# TM8_EVO_Mom.net
KiCad netlist of a schematic drawn in EAGLE
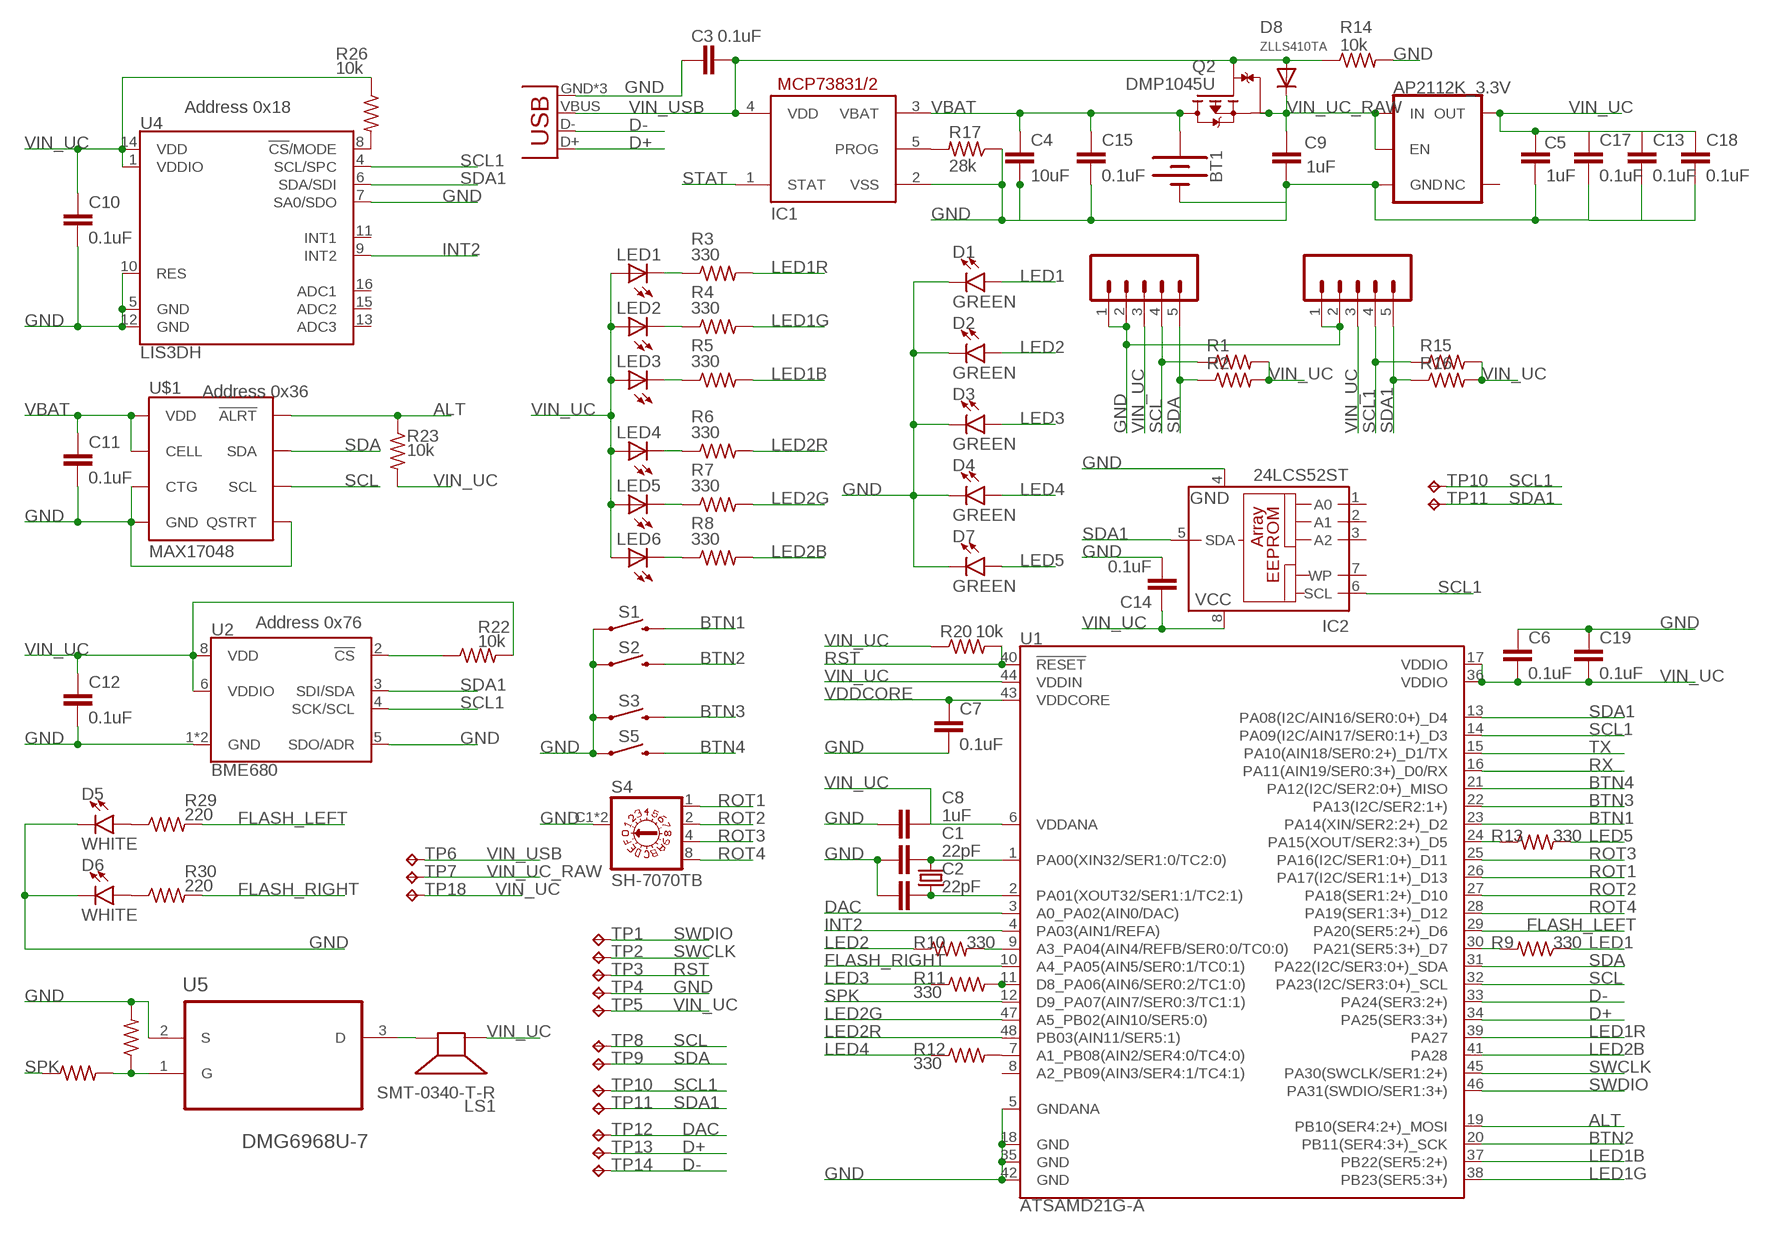
[diagram p0: schematic, sheet 1]

(export (version "E")
  (design (tool "Eeschema 10.0.6"))
  (components
    (comp (ref "AP2112K_3.3V")
      (value "3.3V")
      (footprint "eagle-import:SOT23-5")
      (libsource (lib "eagle-import") (part "V_REG_AP2112K-3.3V"))
    )
    (comp (ref "BT1")
      (value "BATTERY-20MM_SMD_4LEGS_OVERPASTE_INNER")
      (footprint "eagle-import:BATTCON_20MM_4LEGS_OVERPASTE_INNER")
      (libsource (lib "eagle-import") (part "BATTERY-20MM_SMD_4LEGS_OVERPASTE_INNER"))
    )
    (comp (ref "C1")
      (value "22pF")
      (footprint "eagle-import:C0402")
      (libsource (lib "eagle-import") (part "C-EUC0402"))
    )
    (comp (ref "C2")
      (value "22pF")
      (footprint "eagle-import:C0402")
      (libsource (lib "eagle-import") (part "C-EUC0402"))
    )
    (comp (ref "C3")
      (value "0.1uF")
      (footprint "eagle-import:C0402")
      (libsource (lib "eagle-import") (part "C-EUC0402"))
    )
    (comp (ref "C4")
      (value "10uF")
      (footprint "eagle-import:C0402")
      (libsource (lib "eagle-import") (part "C-EUC0402"))
    )
    (comp (ref "C5")
      (value "1uF")
      (footprint "eagle-import:C0402")
      (libsource (lib "eagle-import") (part "C-EUC0402"))
    )
    (comp (ref "C6")
      (value "0.1uF")
      (footprint "eagle-import:C0402")
      (libsource (lib "eagle-import") (part "C-EUC0402"))
    )
    (comp (ref "C7")
      (value "0.1uF")
      (footprint "eagle-import:C0402")
      (libsource (lib "eagle-import") (part "C-EUC0402"))
    )
    (comp (ref "C8")
      (value "1uF")
      (footprint "eagle-import:C0402")
      (libsource (lib "eagle-import") (part "C-EUC0402"))
    )
    (comp (ref "C9")
      (value "1uF")
      (footprint "eagle-import:C0402")
      (libsource (lib "eagle-import") (part "C-EUC0402"))
    )
    (comp (ref "C10")
      (value "0.1uF")
      (footprint "eagle-import:C0402")
      (libsource (lib "eagle-import") (part "C-EUC0402"))
    )
    (comp (ref "C11")
      (value "0.1uF")
      (footprint "eagle-import:C0402")
      (libsource (lib "eagle-import") (part "C-EUC0402"))
    )
    (comp (ref "C12")
      (value "0.1uF")
      (footprint "eagle-import:C0402")
      (libsource (lib "eagle-import") (part "C-EUC0402"))
    )
    (comp (ref "C13")
      (value "0.1uF")
      (footprint "eagle-import:C0402")
      (libsource (lib "eagle-import") (part "C-EUC0402"))
    )
    (comp (ref "C14")
      (value "0.1uF")
      (footprint "eagle-import:C0402")
      (libsource (lib "eagle-import") (part "C-EUC0402"))
    )
    (comp (ref "C15")
      (value "0.1uF")
      (footprint "eagle-import:C0402")
      (libsource (lib "eagle-import") (part "C-EUC0402"))
    )
    (comp (ref "C17")
      (value "0.1uF")
      (footprint "eagle-import:C0402")
      (libsource (lib "eagle-import") (part "C-EUC0402"))
    )
    (comp (ref "C18")
      (value "0.1uF")
      (footprint "eagle-import:C0402")
      (libsource (lib "eagle-import") (part "C-EUC0402"))
    )
    (comp (ref "C19")
      (value "0.1uF")
      (footprint "eagle-import:C0402")
      (libsource (lib "eagle-import") (part "C-EUC0402"))
    )
    (comp (ref "D1")
      (value "GREEN")
      (footprint "eagle-import:LED-1206")
      (libsource (lib "eagle-import") (part "LED-GREEN1206"))
    )
    (comp (ref "D2")
      (value "GREEN")
      (footprint "eagle-import:LED-1206")
      (libsource (lib "eagle-import") (part "LED-GREEN1206"))
    )
    (comp (ref "D3")
      (value "GREEN")
      (footprint "eagle-import:LED-1206")
      (libsource (lib "eagle-import") (part "LED-GREEN1206"))
    )
    (comp (ref "D4")
      (value "GREEN")
      (footprint "eagle-import:LED-1206")
      (libsource (lib "eagle-import") (part "LED-GREEN1206"))
    )
    (comp (ref "D5")
      (value "WHITE")
      (footprint "eagle-import:LED-1206")
      (libsource (lib "eagle-import") (part "LED-WHITE1206"))
    )
    (comp (ref "D6")
      (value "WHITE")
      (footprint "eagle-import:LED-1206")
      (libsource (lib "eagle-import") (part "LED-WHITE1206"))
    )
    (comp (ref "D7")
      (value "GREEN")
      (footprint "eagle-import:LED-1206")
      (libsource (lib "eagle-import") (part "LED-GREEN1206"))
    )
    (comp (ref "D8")
      (value "ZLLS410TA")
      (footprint "eagle-import:SOD-323F")
      (libsource (lib "eagle-import") (part "DIODESOD-323F"))
    )
    (comp (ref "IC1")
      (value "MCP73831/OT")
      (footprint "eagle-import:SOT23-5L")
      (libsource (lib "eagle-import") (part "MCP73831/OT"))
    )
    (comp (ref "IC2")
      (value "24LCS52ST")
      (footprint "eagle-import:TSSOP8")
      (fields (field (name "MF") "MICROCHIP") (field (name "MPN") "24LCS52T/ST"))
      (libsource (lib "eagle-import") (part "24STLCS52"))
    )
    (comp (ref "JP2")
      (value "USB-MICROB")
      (footprint "eagle-import:USB-MICROB")
      (libsource (lib "eagle-import") (part "USB-MICROB"))
    )
    (comp (ref "LCD1")
      (value "CONN_05VERT_FEMALE_HEADER")
      (footprint "eagle-import:1X05_SMD_VERTICAL_COMBO")
      (libsource (lib "eagle-import") (part "CONN_05VERT_FEMALE_HEADER"))
    )
    (comp (ref "LCD2")
      (value "CONN_05VERT_FEMALE_HEADER")
      (footprint "eagle-import:1X05_SMD_VERTICAL_COMBO")
      (libsource (lib "eagle-import") (part "CONN_05VERT_FEMALE_HEADER"))
    )
    (comp (ref "LED1")
      (value "LEDCHIPLED_0805")
      (footprint "eagle-import:CHIPLED_0805")
      (libsource (lib "eagle-import") (part "LEDCHIPLED_0805"))
    )
    (comp (ref "LED2")
      (value "LEDCHIPLED_0805")
      (footprint "eagle-import:CHIPLED_0805")
      (libsource (lib "eagle-import") (part "LEDCHIPLED_0805"))
    )
    (comp (ref "LED3")
      (value "LEDCHIPLED_0805")
      (footprint "eagle-import:CHIPLED_0805")
      (libsource (lib "eagle-import") (part "LEDCHIPLED_0805"))
    )
    (comp (ref "LED4")
      (value "LEDCHIPLED_0805")
      (footprint "eagle-import:CHIPLED_0805")
      (libsource (lib "eagle-import") (part "LEDCHIPLED_0805"))
    )
    (comp (ref "LED5")
      (value "LEDCHIPLED_0805")
      (footprint "eagle-import:CHIPLED_0805")
      (libsource (lib "eagle-import") (part "LEDCHIPLED_0805"))
    )
    (comp (ref "LED6")
      (value "LEDCHIPLED_0805")
      (footprint "eagle-import:CHIPLED_0805")
      (libsource (lib "eagle-import") (part "LEDCHIPLED_0805"))
    )
    (comp (ref "LS1")
      (value "SMT-0340-T-R")
      (footprint "eagle-import:XDCR_SMT-0340-T-R")
      (fields (field (name "MANUFACTURER") "Pui Audio"))
      (libsource (lib "eagle-import") (part "SMT-0340-T-R"))
    )
    (comp (ref "Q2")
      (value "DMP1045U")
      (footprint "eagle-import:SOT91P240X110-3N")
      (fields (field (name "MF") "Diodes Inc."))
      (libsource (lib "eagle-import") (part "DMP1045U"))
    )
    (comp (ref "R1")
      (value "R-US_R0402")
      (footprint "eagle-import:R0402")
      (libsource (lib "eagle-import") (part "adafruit_25768682_R-US_R0402"))
    )
    (comp (ref "R2")
      (value "R-US_R0402")
      (footprint "eagle-import:R0402")
      (libsource (lib "eagle-import") (part "adafruit_25768682_R-US_R0402"))
    )
    (comp (ref "R3")
      (value "330")
      (footprint "eagle-import:R0402")
      (libsource (lib "eagle-import") (part "rcl_334_R-US_R0402"))
    )
    (comp (ref "R4")
      (value "330")
      (footprint "eagle-import:R0402")
      (libsource (lib "eagle-import") (part "rcl_334_R-US_R0402"))
    )
    (comp (ref "R5")
      (value "330")
      (footprint "eagle-import:R0402")
      (libsource (lib "eagle-import") (part "rcl_334_R-US_R0402"))
    )
    (comp (ref "R6")
      (value "330")
      (footprint "eagle-import:R0402")
      (libsource (lib "eagle-import") (part "rcl_334_R-US_R0402"))
    )
    (comp (ref "R7")
      (value "330")
      (footprint "eagle-import:R0402")
      (libsource (lib "eagle-import") (part "rcl_334_R-US_R0402"))
    )
    (comp (ref "R8")
      (value "330")
      (footprint "eagle-import:R0402")
      (libsource (lib "eagle-import") (part "rcl_334_R-US_R0402"))
    )
    (comp (ref "R9")
      (value "330")
      (footprint "eagle-import:R0402")
      (libsource (lib "eagle-import") (part "rcl_334_R-US_R0402"))
    )
    (comp (ref "R10")
      (value "330")
      (footprint "eagle-import:R0402")
      (libsource (lib "eagle-import") (part "rcl_334_R-US_R0402"))
    )
    (comp (ref "R11")
      (value "330")
      (footprint "eagle-import:R0402")
      (libsource (lib "eagle-import") (part "rcl_334_R-US_R0402"))
    )
    (comp (ref "R12")
      (value "330")
      (footprint "eagle-import:R0402")
      (libsource (lib "eagle-import") (part "rcl_334_R-US_R0402"))
    )
    (comp (ref "R13")
      (value "330")
      (footprint "eagle-import:R0402")
      (libsource (lib "eagle-import") (part "rcl_334_R-US_R0402"))
    )
    (comp (ref "R14")
      (value "10k")
      (footprint "eagle-import:R0402")
      (libsource (lib "eagle-import") (part "R-US_R0402"))
    )
    (comp (ref "R15")
      (value "R-US_R0402")
      (footprint "eagle-import:R0402")
      (libsource (lib "eagle-import") (part "adafruit_25768682_R-US_R0402"))
    )
    (comp (ref "R16")
      (value "R-US_R0402")
      (footprint "eagle-import:R0402")
      (libsource (lib "eagle-import") (part "adafruit_25768682_R-US_R0402"))
    )
    (comp (ref "R17")
      (value "28k")
      (footprint "eagle-import:R0402")
      (libsource (lib "eagle-import") (part "adafruit_25768682_R-US_R0402"))
    )
    (comp (ref "R18")
      (value "220")
      (footprint "eagle-import:R0402")
      (libsource (lib "eagle-import") (part "rcl_334_R-US_R0402"))
    )
    (comp (ref "R19")
      (value "220")
      (footprint "eagle-import:R0402")
      (libsource (lib "eagle-import") (part "rcl_334_R-US_R0402"))
    )
    (comp (ref "R20")
      (value "10k")
      (footprint "eagle-import:R0402")
      (libsource (lib "eagle-import") (part "adafruit_25768682_R-US_R0402"))
    )
    (comp (ref "R22")
      (value "10k")
      (footprint "eagle-import:R0402")
      (libsource (lib "eagle-import") (part "rcl_334_R-US_R0402"))
    )
    (comp (ref "R23")
      (value "10k")
      (footprint "eagle-import:R0402")
      (libsource (lib "eagle-import") (part "rcl_334_R-US_R0402"))
    )
    (comp (ref "R26")
      (value "10k")
      (footprint "eagle-import:R0402")
      (libsource (lib "eagle-import") (part "rcl_334_R-US_R0402"))
    )
    (comp (ref "R29")
      (value "220")
      (footprint "eagle-import:R0402")
      (libsource (lib "eagle-import") (part "rcl_334_R-US_R0402"))
    )
    (comp (ref "R30")
      (value "220")
      (footprint "eagle-import:R0402")
      (libsource (lib "eagle-import") (part "rcl_334_R-US_R0402"))
    )
    (comp (ref "S1")
      (value "MOMENTARY-SWITCH-SPST-SMD-6.0X3.5MM")
      (footprint "eagle-import:TACTILE_SWITCH_SMD_6.0X3.5MM")
      (libsource (lib "eagle-import") (part "MOMENTARY-SWITCH-SPST-SMD-6.0X3.5MM"))
    )
    (comp (ref "S2")
      (value "MOMENTARY-SWITCH-SPST-SMD-6.0X3.5MM")
      (footprint "eagle-import:TACTILE_SWITCH_SMD_6.0X3.5MM")
      (libsource (lib "eagle-import") (part "MOMENTARY-SWITCH-SPST-SMD-6.0X3.5MM"))
    )
    (comp (ref "S3")
      (value "MOMENTARY-SWITCH-SPST-SMD-6.0X3.5MM")
      (footprint "eagle-import:TACTILE_SWITCH_SMD_6.0X3.5MM")
      (libsource (lib "eagle-import") (part "MOMENTARY-SWITCH-SPST-SMD-6.0X3.5MM"))
    )
    (comp (ref "S4")
      (value "SH-7070TB")
      (footprint "eagle-import:SH-7070B")
      (fields (field (name "MF") "Nidec Copal"))
      (libsource (lib "eagle-import") (part "SH-7070TB"))
    )
    (comp (ref "S5")
      (value "MOMENTARY-SWITCH-SPST-SMD-6.0X3.5MM")
      (footprint "eagle-import:TACTILE_SWITCH_SMD_6.0X3.5MM")
      (libsource (lib "eagle-import") (part "MOMENTARY-SWITCH-SPST-SMD-6.0X3.5MM"))
    )
    (comp (ref "TP1")
      (value "TPTP14R")
      (footprint "eagle-import:TP14R")
      (libsource (lib "eagle-import") (part "TPTP14R"))
    )
    (comp (ref "TP2")
      (value "TPTP14R")
      (footprint "eagle-import:TP14R")
      (libsource (lib "eagle-import") (part "TPTP14R"))
    )
    (comp (ref "TP3")
      (value "TPTP14R")
      (footprint "eagle-import:TP14R")
      (libsource (lib "eagle-import") (part "TPTP14R"))
    )
    (comp (ref "TP4")
      (value "TPTP14R")
      (footprint "eagle-import:TP14R")
      (libsource (lib "eagle-import") (part "TPTP14R"))
    )
    (comp (ref "TP5")
      (value "TPTP14R")
      (footprint "eagle-import:TP14R")
      (libsource (lib "eagle-import") (part "TPTP14R"))
    )
    (comp (ref "TP6")
      (value "TPTP14R")
      (footprint "eagle-import:TP14R")
      (libsource (lib "eagle-import") (part "TPTP14R"))
    )
    (comp (ref "TP7")
      (value "TPTP14R")
      (footprint "eagle-import:TP14R")
      (libsource (lib "eagle-import") (part "TPTP14R"))
    )
    (comp (ref "TP8")
      (value "TPTP14R")
      (footprint "eagle-import:TP14R")
      (libsource (lib "eagle-import") (part "TPTP14R"))
    )
    (comp (ref "TP9")
      (value "TPTP14R")
      (footprint "eagle-import:TP14R")
      (libsource (lib "eagle-import") (part "TPTP14R"))
    )
    (comp (ref "TP10")
      (value "TPTP14R")
      (footprint "eagle-import:TP14R")
      (libsource (lib "eagle-import") (part "TPTP14R"))
    )
    (comp (ref "TP11")
      (value "TPTP14R")
      (footprint "eagle-import:TP14R")
      (libsource (lib "eagle-import") (part "TPTP14R"))
    )
    (comp (ref "TP12")
      (value "TPTP14R")
      (footprint "eagle-import:TP14R")
      (libsource (lib "eagle-import") (part "TPTP14R"))
    )
    (comp (ref "TP13")
      (value "TPTP14R")
      (footprint "eagle-import:TP14R")
      (libsource (lib "eagle-import") (part "TPTP14R"))
    )
    (comp (ref "TP14")
      (value "TPTP14R")
      (footprint "eagle-import:TP14R")
      (libsource (lib "eagle-import") (part "TPTP14R"))
    )
    (comp (ref "TP15")
      (value "TPTP14R")
      (footprint "eagle-import:TP14R")
      (libsource (lib "eagle-import") (part "TPTP14R"))
    )
    (comp (ref "TP16")
      (value "TPTP14R")
      (footprint "eagle-import:TP14R")
      (libsource (lib "eagle-import") (part "TPTP14R"))
    )
    (comp (ref "TP18")
      (value "TPTP14R")
      (footprint "eagle-import:TP14R")
      (libsource (lib "eagle-import") (part "TPTP14R"))
    )
    (comp (ref "U$1")
      (value "MAX17048")
      (footprint "eagle-import:DFN-8")
      (libsource (lib "eagle-import") (part "MAX17048DFN8"))
    )
    (comp (ref "U1")
      (value "ATSAMD21G-A")
      (footprint "eagle-import:TQFP-48")
      (libsource (lib "eagle-import") (part "ATSAMD21G-A"))
    )
    (comp (ref "U2")
      (value "BME680")
      (footprint "eagle-import:LGA3.0X3.0")
      (libsource (lib "eagle-import") (part "BME680-LGA"))
    )
    (comp (ref "U4")
      (value "LIS3DH")
      (footprint "eagle-import:LGA-16-3X3")
      (libsource (lib "eagle-import") (part "LIS3DH"))
    )
    (comp (ref "U5")
      (value "DMG6968U-7")
      (footprint "eagle-import:SOT95P240X110-3N")
      (fields (field (name "MF") "Diodes Inc."))
      (libsource (lib "eagle-import") (part "DMG6968U-7"))
    )
    (comp (ref "Y1")
      (value "32.768kHz")
      (footprint "eagle-import:CRYSTAL-SMD-3.2X1.5MM")
      (libsource (lib "eagle-import") (part "CRYSTAL-32.768KHZSMD-3.2X1.5"))
    )
  )
  (nets
    (net (code "1") (name "/ALT") (class "Default")
      (node (ref "R23") (pin "1") (pinfunction "1_1") (pintype "passive"))
      (node (ref "U$1") (pin "P$5") (pinfunction "~{ALRT}_P$5") (pintype "bidirectional"))
      (node (ref "U1") (pin "19") (pinfunction "PB10(SER4:2+)_MOSI_19") (pintype "bidirectional"))
    )
    (net (code "2") (name "/BTN1") (class "Default")
      (node (ref "S1") (pin "2") (pinfunction "2_2") (pintype "passive"))
      (node (ref "U1") (pin "23") (pinfunction "PA14(XIN/SER2:2+)_D2_23") (pintype "bidirectional"))
    )
    (net (code "3") (name "/BTN2") (class "Default")
      (node (ref "S2") (pin "2") (pinfunction "2_2") (pintype "passive"))
      (node (ref "U1") (pin "20") (pinfunction "PB11(SER4:3+)_SCK_20") (pintype "bidirectional"))
    )
    (net (code "4") (name "/BTN3") (class "Default")
      (node (ref "S3") (pin "2") (pinfunction "2_2") (pintype "passive"))
      (node (ref "U1") (pin "22") (pinfunction "PA13(I2C/SER2:1+)_22") (pintype "bidirectional"))
    )
    (net (code "5") (name "/BTN4") (class "Default")
      (node (ref "S5") (pin "2") (pinfunction "2_2") (pintype "passive"))
      (node (ref "U1") (pin "21") (pinfunction "PA12(I2C/SER2:0+)_MISO_21") (pintype "bidirectional"))
    )
    (net (code "6") (name "/D+") (class "Default")
      (node (ref "JP2") (pin "D+") (pinfunction "D+_D+") (pintype "bidirectional"))
      (node (ref "TP13") (pin "TP") (pinfunction "TP_TP") (pintype "input"))
      (node (ref "U1") (pin "34") (pinfunction "PA25(SER3:3+)_34") (pintype "bidirectional"))
    )
    (net (code "7") (name "/D-") (class "Default")
      (node (ref "JP2") (pin "D-") (pinfunction "D-_D-") (pintype "bidirectional"))
      (node (ref "TP14") (pin "TP") (pinfunction "TP_TP") (pintype "input"))
      (node (ref "U1") (pin "33") (pinfunction "PA24(SER3:2+)_33") (pintype "bidirectional"))
    )
    (net (code "8") (name "/DAC") (class "Default")
      (node (ref "TP12") (pin "TP") (pinfunction "TP_TP") (pintype "input"))
      (node (ref "U1") (pin "3") (pinfunction "A0_PA02(AIN0/DAC)_3") (pintype "bidirectional"))
    )
    (net (code "9") (name "/FLASH_LEFT") (class "Default")
      (node (ref "R29") (pin "2") (pinfunction "2_2") (pintype "passive"))
      (node (ref "U1") (pin "29") (pinfunction "PA20(SER5:2+)_D6_29") (pintype "bidirectional"))
    )
    (net (code "10") (name "/FLASH_RIGHT") (class "Default")
      (node (ref "R30") (pin "2") (pinfunction "2_2") (pintype "passive"))
      (node (ref "U1") (pin "10") (pinfunction "A4_PA05(AIN5/SER0:1/TC0:1)_10") (pintype "bidirectional"))
    )
    (net (code "11") (name "/GND") (class "Default")
      (node (ref "AP2112K_3.3V") (pin "2") (pinfunction "GND_2") (pintype "input"))
      (node (ref "BT1") (pin "2") (pinfunction "-_2") (pintype "power_in"))
      (node (ref "C1") (pin "1") (pinfunction "1_1") (pintype "passive"))
      (node (ref "C10") (pin "2") (pinfunction "2_2") (pintype "passive"))
      (node (ref "C11") (pin "2") (pinfunction "2_2") (pintype "passive"))
      (node (ref "C12") (pin "2") (pinfunction "2_2") (pintype "passive"))
      (node (ref "C13") (pin "2") (pinfunction "2_2") (pintype "passive"))
      (node (ref "C14") (pin "2") (pinfunction "2_2") (pintype "passive"))
      (node (ref "C15") (pin "2") (pinfunction "2_2") (pintype "passive"))
      (node (ref "C17") (pin "2") (pinfunction "2_2") (pintype "passive"))
      (node (ref "C18") (pin "2") (pinfunction "2_2") (pintype "passive"))
      (node (ref "C19") (pin "1") (pinfunction "1_1") (pintype "passive"))
      (node (ref "C2") (pin "1") (pinfunction "1_1") (pintype "passive"))
      (node (ref "C3") (pin "1") (pinfunction "1_1") (pintype "passive"))
      (node (ref "C4") (pin "2") (pinfunction "2_2") (pintype "passive"))
      (node (ref "C5") (pin "2") (pinfunction "2_2") (pintype "passive"))
      (node (ref "C6") (pin "1") (pinfunction "1_1") (pintype "passive"))
      (node (ref "C7") (pin "2") (pinfunction "2_2") (pintype "passive"))
      (node (ref "C8") (pin "1") (pinfunction "1_1") (pintype "passive"))
      (node (ref "C9") (pin "2") (pinfunction "2_2") (pintype "passive"))
      (node (ref "D1") (pin "C") (pinfunction "C_C") (pintype "passive"))
      (node (ref "D2") (pin "C") (pinfunction "C_C") (pintype "passive"))
      (node (ref "D3") (pin "C") (pinfunction "C_C") (pintype "passive"))
      (node (ref "D4") (pin "C") (pinfunction "C_C") (pintype "passive"))
      (node (ref "D5") (pin "C") (pinfunction "C_C") (pintype "passive"))
      (node (ref "D6") (pin "C") (pinfunction "C_C") (pintype "passive"))
      (node (ref "D7") (pin "C") (pinfunction "C_C") (pintype "passive"))
      (node (ref "IC1") (pin "2") (pinfunction "VSS_2") (pintype "power_in"))
      (node (ref "IC2") (pin "4") (pinfunction "GND_4") (pintype "power_in"))
      (node (ref "JP2") (pin "GND") (pinfunction "GND_GND") (pintype "bidirectional"))
      (node (ref "JP2") (pin "MT1") (pinfunction "GND_MT1") (pintype "bidirectional"))
      (node (ref "JP2") (pin "MT2") (pinfunction "GND_MT2") (pintype "bidirectional"))
      (node (ref "LCD1") (pin "1") (pinfunction "1_1") (pintype "passive"))
      (node (ref "LCD1") (pin "2") (pinfunction "2_2") (pintype "passive"))
      (node (ref "LCD2") (pin "1") (pinfunction "1_1") (pintype "passive"))
      (node (ref "LCD2") (pin "2") (pinfunction "2_2") (pintype "passive"))
      (node (ref "R14") (pin "2") (pinfunction "2_2") (pintype "passive"))
      (node (ref "R17") (pin "1") (pinfunction "1_1") (pintype "passive"))
      (node (ref "R19") (pin "2") (pinfunction "2_2") (pintype "passive"))
      (node (ref "S1") (pin "1") (pinfunction "1_1") (pintype "passive"))
      (node (ref "S2") (pin "1") (pinfunction "1_1") (pintype "passive"))
      (node (ref "S3") (pin "1") (pinfunction "1_1") (pintype "passive"))
      (node (ref "S4") (pin "C1") (pinfunction "C_C1") (pintype "passive"))
      (node (ref "S4") (pin "C2") (pinfunction "C_C2") (pintype "passive"))
      (node (ref "S5") (pin "1") (pinfunction "1_1") (pintype "passive"))
      (node (ref "TP4") (pin "TP") (pinfunction "TP_TP") (pintype "input"))
      (node (ref "U$1") (pin "P$1") (pinfunction "CTG_P$1") (pintype "input"))
      (node (ref "U$1") (pin "P$4") (pinfunction "GND_P$4") (pintype "bidirectional"))
      (node (ref "U$1") (pin "P$6") (pinfunction "QSTRT_P$6") (pintype "bidirectional"))
      (node (ref "U$1") (pin "P$9") (pinfunction "GND_P$9") (pintype "bidirectional"))
      (node (ref "U1") (pin "18") (pinfunction "GND_18") (pintype "bidirectional"))
      (node (ref "U1") (pin "35") (pinfunction "GND_35") (pintype "bidirectional"))
      (node (ref "U1") (pin "42") (pinfunction "GND_42") (pintype "bidirectional"))
      (node (ref "U1") (pin "5") (pinfunction "GNDANA_5") (pintype "bidirectional"))
      (node (ref "U2") (pin "1") (pinfunction "GND_1") (pintype "bidirectional"))
      (node (ref "U2") (pin "5") (pinfunction "SDO/ADR_5") (pintype "bidirectional"))
      (node (ref "U2") (pin "7") (pinfunction "GND_7") (pintype "bidirectional"))
      (node (ref "U4") (pin "10") (pinfunction "RES_10") (pintype "bidirectional"))
      (node (ref "U4") (pin "12") (pinfunction "GND_12") (pintype "bidirectional"))
      (node (ref "U4") (pin "5") (pinfunction "GND_5") (pintype "bidirectional"))
      (node (ref "U4") (pin "7") (pinfunction "SA0/SDO_7") (pintype "bidirectional"))
      (node (ref "U5") (pin "2") (pinfunction "S_2") (pintype "passive"))
    )
    (net (code "12") (name "/INT2") (class "Default")
      (node (ref "U1") (pin "4") (pinfunction "PA03(AIN1/REFA)_4") (pintype "bidirectional"))
      (node (ref "U4") (pin "9") (pinfunction "INT2_9") (pintype "bidirectional"))
    )
    (net (code "13") (name "/LED1") (class "Default")
      (node (ref "D1") (pin "A") (pinfunction "A_A") (pintype "passive"))
      (node (ref "R9") (pin "1") (pinfunction "1_1") (pintype "passive"))
    )
    (net (code "14") (name "/LED1B") (class "Default")
      (node (ref "R5") (pin "2") (pinfunction "2_2") (pintype "passive"))
      (node (ref "U1") (pin "37") (pinfunction "PB22(SER5:2+)_37") (pintype "bidirectional"))
    )
    (net (code "15") (name "/LED1G") (class "Default")
      (node (ref "R4") (pin "2") (pinfunction "2_2") (pintype "passive"))
      (node (ref "U1") (pin "38") (pinfunction "PB23(SER5:3+)_38") (pintype "bidirectional"))
    )
    (net (code "16") (name "/LED1R") (class "Default")
      (node (ref "R3") (pin "2") (pinfunction "2_2") (pintype "passive"))
      (node (ref "U1") (pin "39") (pinfunction "PA27_39") (pintype "bidirectional"))
    )
    (net (code "17") (name "/LED2") (class "Default")
      (node (ref "D2") (pin "A") (pinfunction "A_A") (pintype "passive"))
      (node (ref "R10") (pin "1") (pinfunction "1_1") (pintype "passive"))
    )
    (net (code "18") (name "/LED2B") (class "Default")
      (node (ref "R8") (pin "2") (pinfunction "2_2") (pintype "passive"))
      (node (ref "U1") (pin "41") (pinfunction "PA28_41") (pintype "bidirectional"))
    )
    (net (code "19") (name "/LED2G") (class "Default")
      (node (ref "R7") (pin "2") (pinfunction "2_2") (pintype "passive"))
      (node (ref "U1") (pin "47") (pinfunction "A5_PB02(AIN10/SER5:0)_47") (pintype "bidirectional"))
    )
    (net (code "20") (name "/LED2R") (class "Default")
      (node (ref "R6") (pin "2") (pinfunction "2_2") (pintype "passive"))
      (node (ref "U1") (pin "48") (pinfunction "PB03(AIN11/SER5:1)_48") (pintype "bidirectional"))
    )
    (net (code "21") (name "/LED3") (class "Default")
      (node (ref "D3") (pin "A") (pinfunction "A_A") (pintype "passive"))
      (node (ref "R11") (pin "1") (pinfunction "1_1") (pintype "passive"))
    )
    (net (code "22") (name "/LED4") (class "Default")
      (node (ref "D4") (pin "A") (pinfunction "A_A") (pintype "passive"))
      (node (ref "R12") (pin "1") (pinfunction "1_1") (pintype "passive"))
    )
    (net (code "23") (name "/LED5") (class "Default")
      (node (ref "D7") (pin "A") (pinfunction "A_A") (pintype "passive"))
      (node (ref "R13") (pin "2") (pinfunction "2_2") (pintype "passive"))
    )
    (net (code "24") (name "/ROT1") (class "Default")
      (node (ref "S4") (pin "1") (pinfunction "1_1") (pintype "passive"))
      (node (ref "U1") (pin "26") (pinfunction "PA17(I2C/SER1:1+)_D13_26") (pintype "bidirectional"))
    )
    (net (code "25") (name "/ROT2") (class "Default")
      (node (ref "S4") (pin "2") (pinfunction "2_2") (pintype "passive"))
      (node (ref "U1") (pin "27") (pinfunction "PA18(SER1:2+)_D10_27") (pintype "bidirectional"))
    )
    (net (code "26") (name "/ROT3") (class "Default")
      (node (ref "S4") (pin "4") (pinfunction "4_4") (pintype "passive"))
      (node (ref "U1") (pin "25") (pinfunction "PA16(I2C/SER1:0+)_D11_25") (pintype "bidirectional"))
    )
    (net (code "27") (name "/ROT4") (class "Default")
      (node (ref "S4") (pin "8") (pinfunction "8_8") (pintype "passive"))
      (node (ref "U1") (pin "28") (pinfunction "PA19(SER1:3+)_D12_28") (pintype "bidirectional"))
    )
    (net (code "28") (name "/RST") (class "Default")
      (node (ref "R20") (pin "2") (pinfunction "2_2") (pintype "passive"))
      (node (ref "TP3") (pin "TP") (pinfunction "TP_TP") (pintype "input"))
      (node (ref "U1") (pin "40") (pinfunction "~{RESET}_40") (pintype "bidirectional"))
    )
    (net (code "29") (name "/RX") (class "Default")
      (node (ref "U1") (pin "16") (pinfunction "PA11(AIN19/SER0:3+)_D0/RX_16") (pintype "bidirectional"))
    )
    (net (code "30") (name "/SCL") (class "Default")
      (node (ref "LCD1") (pin "4") (pinfunction "4_4") (pintype "passive"))
      (node (ref "R1") (pin "1") (pinfunction "1_1") (pintype "passive"))
      (node (ref "TP8") (pin "TP") (pinfunction "TP_TP") (pintype "input"))
      (node (ref "U$1") (pin "P$7") (pinfunction "SCL_P$7") (pintype "output"))
      (node (ref "U1") (pin "32") (pinfunction "PA23(I2C/SER3:0+)_SCL_32") (pintype "bidirectional"))
    )
    (net (code "31") (name "/SCL1") (class "Default")
      (node (ref "IC2") (pin "6") (pinfunction "SCL_6") (pintype "input"))
      (node (ref "LCD2") (pin "4") (pinfunction "4_4") (pintype "passive"))
      (node (ref "R15") (pin "1") (pinfunction "1_1") (pintype "passive"))
      (node (ref "TP10") (pin "TP") (pinfunction "TP_TP") (pintype "input"))
      (node (ref "TP15") (pin "TP") (pinfunction "TP_TP") (pintype "input"))
      (node (ref "U1") (pin "14") (pinfunction "PA09(I2C/AIN17/SER0:1+)_D3_14") (pintype "bidirectional"))
      (node (ref "U2") (pin "4") (pinfunction "SCK/SCL_4") (pintype "bidirectional"))
      (node (ref "U4") (pin "4") (pinfunction "SCL/SPC_4") (pintype "bidirectional"))
    )
    (net (code "32") (name "/SDA") (class "Default")
      (node (ref "LCD1") (pin "5") (pinfunction "5_5") (pintype "passive"))
      (node (ref "R2") (pin "1") (pinfunction "1_1") (pintype "passive"))
      (node (ref "TP9") (pin "TP") (pinfunction "TP_TP") (pintype "input"))
      (node (ref "U$1") (pin "P$8") (pinfunction "SDA_P$8") (pintype "input"))
      (node (ref "U1") (pin "31") (pinfunction "PA22(I2C/SER3:0+)_SDA_31") (pintype "bidirectional"))
    )
    (net (code "33") (name "/SDA1") (class "Default")
      (node (ref "IC2") (pin "5") (pinfunction "SDA_5") (pintype "bidirectional"))
      (node (ref "LCD2") (pin "5") (pinfunction "5_5") (pintype "passive"))
      (node (ref "R16") (pin "1") (pinfunction "1_1") (pintype "passive"))
      (node (ref "TP11") (pin "TP") (pinfunction "TP_TP") (pintype "input"))
      (node (ref "TP16") (pin "TP") (pinfunction "TP_TP") (pintype "input"))
      (node (ref "U1") (pin "13") (pinfunction "PA08(I2C/AIN16/SER0:0+)_D4_13") (pintype "bidirectional"))
      (node (ref "U2") (pin "3") (pinfunction "SDI/SDA_3") (pintype "bidirectional"))
      (node (ref "U4") (pin "6") (pinfunction "SDA/SDI_6") (pintype "bidirectional"))
    )
    (net (code "34") (name "/SPK") (class "Default")
      (node (ref "R18") (pin "1") (pinfunction "1_1") (pintype "passive"))
      (node (ref "U1") (pin "12") (pinfunction "D9_PA07(AIN7/SER0:3/TC1:1)_12") (pintype "bidirectional"))
    )
    (net (code "35") (name "/STAT") (class "Default")
      (node (ref "IC1") (pin "1") (pinfunction "STAT_1") (pintype "output"))
    )
    (net (code "36") (name "/SWCLK") (class "Default")
      (node (ref "TP2") (pin "TP") (pinfunction "TP_TP") (pintype "input"))
      (node (ref "U1") (pin "45") (pinfunction "PA30(SWCLK/SER1:2+)_45") (pintype "bidirectional"))
    )
    (net (code "37") (name "/SWDIO") (class "Default")
      (node (ref "TP1") (pin "TP") (pinfunction "TP_TP") (pintype "input"))
      (node (ref "U1") (pin "46") (pinfunction "PA31(SWDIO/SER1:3+)_46") (pintype "bidirectional"))
    )
    (net (code "38") (name "/TX") (class "Default")
      (node (ref "U1") (pin "15") (pinfunction "PA10(AIN18/SER0:2+)_D1/TX_15") (pintype "bidirectional"))
    )
    (net (code "39") (name "/VBAT") (class "Default")
      (node (ref "BT1") (pin "1") (pinfunction "+_1") (pintype "power_in"))
      (node (ref "C11") (pin "1") (pinfunction "1_1") (pintype "passive"))
      (node (ref "C15") (pin "1") (pinfunction "1_1") (pintype "passive"))
      (node (ref "C4") (pin "1") (pinfunction "1_1") (pintype "passive"))
      (node (ref "IC1") (pin "3") (pinfunction "VBAT_3") (pintype "bidirectional"))
      (node (ref "Q2") (pin "3") (pinfunction "D_3") (pintype "passive"))
      (node (ref "U$1") (pin "P$2") (pinfunction "CELL_P$2") (pintype "input"))
      (node (ref "U$1") (pin "P$3") (pinfunction "VDD_P$3") (pintype "bidirectional"))
    )
    (net (code "40") (name "/VDDCORE") (class "Default")
      (node (ref "C7") (pin "1") (pinfunction "1_1") (pintype "passive"))
      (node (ref "U1") (pin "43") (pinfunction "VDDCORE_43") (pintype "bidirectional"))
    )
    (net (code "41") (name "/VIN_UC") (class "Default")
      (node (ref "AP2112K_3.3V") (pin "5") (pinfunction "OUT_5") (pintype "passive"))
      (node (ref "C10") (pin "1") (pinfunction "1_1") (pintype "passive"))
      (node (ref "C12") (pin "1") (pinfunction "1_1") (pintype "passive"))
      (node (ref "C13") (pin "1") (pinfunction "1_1") (pintype "passive"))
      (node (ref "C14") (pin "1") (pinfunction "1_1") (pintype "passive"))
      (node (ref "C17") (pin "1") (pinfunction "1_1") (pintype "passive"))
      (node (ref "C18") (pin "1") (pinfunction "1_1") (pintype "passive"))
      (node (ref "C19") (pin "2") (pinfunction "2_2") (pintype "passive"))
      (node (ref "C5") (pin "1") (pinfunction "1_1") (pintype "passive"))
      (node (ref "C6") (pin "2") (pinfunction "2_2") (pintype "passive"))
      (node (ref "C8") (pin "2") (pinfunction "2_2") (pintype "passive"))
      (node (ref "IC2") (pin "8") (pinfunction "VCC_8") (pintype "power_in"))
      (node (ref "LCD1") (pin "3") (pinfunction "3_3") (pintype "passive"))
      (node (ref "LCD2") (pin "3") (pinfunction "3_3") (pintype "passive"))
      (node (ref "LED1") (pin "A") (pinfunction "A_A") (pintype "passive"))
      (node (ref "LED2") (pin "A") (pinfunction "A_A") (pintype "passive"))
      (node (ref "LED3") (pin "A") (pinfunction "A_A") (pintype "passive"))
      (node (ref "LED4") (pin "A") (pinfunction "A_A") (pintype "passive"))
      (node (ref "LED5") (pin "A") (pinfunction "A_A") (pintype "passive"))
      (node (ref "LED6") (pin "A") (pinfunction "A_A") (pintype "passive"))
      (node (ref "LS1") (pin "P") (pinfunction "P_P") (pintype "passive"))
      (node (ref "R1") (pin "2") (pinfunction "2_2") (pintype "passive"))
      (node (ref "R15") (pin "2") (pinfunction "2_2") (pintype "passive"))
      (node (ref "R16") (pin "2") (pinfunction "2_2") (pintype "passive"))
      (node (ref "R2") (pin "2") (pinfunction "2_2") (pintype "passive"))
      (node (ref "R20") (pin "1") (pinfunction "1_1") (pintype "passive"))
      (node (ref "R22") (pin "2") (pinfunction "2_2") (pintype "passive"))
      (node (ref "R23") (pin "2") (pinfunction "2_2") (pintype "passive"))
      (node (ref "R26") (pin "1") (pinfunction "1_1") (pintype "passive"))
      (node (ref "TP18") (pin "TP") (pinfunction "TP_TP") (pintype "input"))
      (node (ref "TP5") (pin "TP") (pinfunction "TP_TP") (pintype "input"))
      (node (ref "U1") (pin "17") (pinfunction "VDDIO_17") (pintype "bidirectional"))
      (node (ref "U1") (pin "36") (pinfunction "VDDIO_36") (pintype "bidirectional"))
      (node (ref "U1") (pin "44") (pinfunction "VDDIN_44") (pintype "bidirectional"))
      (node (ref "U1") (pin "6") (pinfunction "VDDANA_6") (pintype "bidirectional"))
      (node (ref "U2") (pin "6") (pinfunction "VDDIO_6") (pintype "bidirectional"))
      (node (ref "U2") (pin "8") (pinfunction "VDD_8") (pintype "bidirectional"))
      (node (ref "U4") (pin "1") (pinfunction "VDDIO_1") (pintype "bidirectional"))
      (node (ref "U4") (pin "14") (pinfunction "VDD_14") (pintype "bidirectional"))
    )
    (net (code "42") (name "/VIN_UC_RAW") (class "Default")
      (node (ref "AP2112K_3.3V") (pin "1") (pinfunction "IN_1") (pintype "input"))
      (node (ref "AP2112K_3.3V") (pin "3") (pinfunction "EN_3") (pintype "input"))
      (node (ref "C9") (pin "1") (pinfunction "1_1") (pintype "passive"))
      (node (ref "D8") (pin "C") (pinfunction "C_C") (pintype "passive"))
      (node (ref "Q2") (pin "2") (pinfunction "S_2") (pintype "passive"))
      (node (ref "TP7") (pin "TP") (pinfunction "TP_TP") (pintype "input"))
    )
    (net (code "43") (name "/VIN_USB") (class "Default")
      (node (ref "C3") (pin "2") (pinfunction "2_2") (pintype "passive"))
      (node (ref "D8") (pin "A") (pinfunction "A_A") (pintype "passive"))
      (node (ref "IC1") (pin "4") (pinfunction "VDD_4") (pintype "power_in"))
      (node (ref "JP2") (pin "VBUS") (pinfunction "VBUS_VBUS") (pintype "bidirectional"))
      (node (ref "Q2") (pin "1") (pinfunction "G_1") (pintype "passive"))
      (node (ref "R14") (pin "1") (pinfunction "1_1") (pintype "passive"))
      (node (ref "TP6") (pin "TP") (pinfunction "TP_TP") (pintype "input"))
    )
    (net (code "44") (name "Net-(D5-PadA)") (class "Default")
      (node (ref "D5") (pin "A") (pinfunction "A_A") (pintype "passive"))
      (node (ref "R29") (pin "1") (pinfunction "1_1") (pintype "passive"))
    )
    (net (code "45") (name "Net-(D6-PadA)") (class "Default")
      (node (ref "D6") (pin "A") (pinfunction "A_A") (pintype "passive"))
      (node (ref "R30") (pin "1") (pinfunction "1_1") (pintype "passive"))
    )
    (net (code "46") (name "Net-(IC1-PROG)") (class "Default")
      (node (ref "IC1") (pin "5") (pinfunction "PROG_5") (pintype "input"))
      (node (ref "R17") (pin "2") (pinfunction "2_2") (pintype "passive"))
    )
    (net (code "47") (name "Net-(LED1-PadC)") (class "Default")
      (node (ref "LED1") (pin "C") (pinfunction "C_C") (pintype "passive"))
      (node (ref "R3") (pin "1") (pinfunction "1_1") (pintype "passive"))
    )
    (net (code "48") (name "Net-(LED2-PadC)") (class "Default")
      (node (ref "LED2") (pin "C") (pinfunction "C_C") (pintype "passive"))
      (node (ref "R4") (pin "1") (pinfunction "1_1") (pintype "passive"))
    )
    (net (code "49") (name "Net-(LED3-PadC)") (class "Default")
      (node (ref "LED3") (pin "C") (pinfunction "C_C") (pintype "passive"))
      (node (ref "R5") (pin "1") (pinfunction "1_1") (pintype "passive"))
    )
    (net (code "50") (name "Net-(LED4-PadC)") (class "Default")
      (node (ref "LED4") (pin "C") (pinfunction "C_C") (pintype "passive"))
      (node (ref "R6") (pin "1") (pinfunction "1_1") (pintype "passive"))
    )
    (net (code "51") (name "Net-(LED5-PadC)") (class "Default")
      (node (ref "LED5") (pin "C") (pinfunction "C_C") (pintype "passive"))
      (node (ref "R7") (pin "1") (pinfunction "1_1") (pintype "passive"))
    )
    (net (code "52") (name "Net-(LED6-PadC)") (class "Default")
      (node (ref "LED6") (pin "C") (pinfunction "C_C") (pintype "passive"))
      (node (ref "R8") (pin "1") (pinfunction "1_1") (pintype "passive"))
    )
    (net (code "53") (name "Net-(U1-A1_PB08(AIN2{slash}SER4:0{slash}TC4:0))") (class "Default")
      (node (ref "R12") (pin "2") (pinfunction "2_2") (pintype "passive"))
      (node (ref "U1") (pin "7") (pinfunction "A1_PB08(AIN2/SER4:0/TC4:0)_7") (pintype "bidirectional"))
    )
    (net (code "54") (name "Net-(U1-A3_PA04(AIN4{slash}REFB{slash}SER0:0{slash}TC0:0))") (class "Default")
      (node (ref "R10") (pin "2") (pinfunction "2_2") (pintype "passive"))
      (node (ref "U1") (pin "9") (pinfunction "A3_PA04(AIN4/REFB/SER0:0/TC0:0)_9") (pintype "bidirectional"))
    )
    (net (code "55") (name "Net-(U1-D8_PA06(AIN6{slash}SER0:2{slash}TC1:0))") (class "Default")
      (node (ref "R11") (pin "2") (pinfunction "2_2") (pintype "passive"))
      (node (ref "U1") (pin "11") (pinfunction "D8_PA06(AIN6/SER0:2/TC1:0)_11") (pintype "bidirectional"))
    )
    (net (code "56") (name "Net-(U1-PA00(XIN32{slash}SER1:0{slash}TC2:0))") (class "Default")
      (node (ref "C1") (pin "2") (pinfunction "2_2") (pintype "passive"))
      (node (ref "U1") (pin "1") (pinfunction "PA00(XIN32/SER1:0/TC2:0)_1") (pintype "bidirectional"))
      (node (ref "Y1") (pin "P$2") (pinfunction "2_P$2") (pintype "passive"))
    )
    (net (code "57") (name "Net-(U1-PA01(XOUT32{slash}SER1:1{slash}TC2:1))") (class "Default")
      (node (ref "C2") (pin "2") (pinfunction "2_2") (pintype "passive"))
      (node (ref "U1") (pin "2") (pinfunction "PA01(XOUT32/SER1:1/TC2:1)_2") (pintype "bidirectional"))
      (node (ref "Y1") (pin "P$1") (pinfunction "1_P$1") (pintype "passive"))
    )
    (net (code "58") (name "Net-(U1-PA15(XOUT{slash}SER2:3+)_D5)") (class "Default")
      (node (ref "R13") (pin "1") (pinfunction "1_1") (pintype "passive"))
      (node (ref "U1") (pin "24") (pinfunction "PA15(XOUT/SER2:3+)_D5_24") (pintype "bidirectional"))
    )
    (net (code "59") (name "Net-(U1-PA21(SER5:3+)_D7)") (class "Default")
      (node (ref "R9") (pin "2") (pinfunction "2_2") (pintype "passive"))
      (node (ref "U1") (pin "30") (pinfunction "PA21(SER5:3+)_D7_30") (pintype "bidirectional"))
    )
    (net (code "60") (name "Net-(U2-~{CS})") (class "Default")
      (node (ref "R22") (pin "1") (pinfunction "1_1") (pintype "passive"))
      (node (ref "U2") (pin "2") (pinfunction "~{CS}_2") (pintype "bidirectional"))
    )
    (net (code "61") (name "Net-(U4-~{CS}{slash}MODE)") (class "Default")
      (node (ref "R26") (pin "2") (pinfunction "2_2") (pintype "passive"))
      (node (ref "U4") (pin "8") (pinfunction "~{CS}/MODE_8") (pintype "bidirectional"))
    )
    (net (code "62") (name "Net-(U5-D)") (class "Default")
      (node (ref "LS1") (pin "N") (pinfunction "N_N") (pintype "passive"))
      (node (ref "U5") (pin "3") (pinfunction "D_3") (pintype "output"))
    )
    (net (code "63") (name "Net-(U5-G)") (class "Default")
      (node (ref "R18") (pin "2") (pinfunction "2_2") (pintype "passive"))
      (node (ref "R19") (pin "1") (pinfunction "1_1") (pintype "passive"))
      (node (ref "U5") (pin "1") (pinfunction "G_1") (pintype "power_in"))
    )
    (net (code "64") (name "unconnected-(AP2112K_3.3V-NC-Pad4)") (class "Default")
      (node (ref "AP2112K_3.3V") (pin "4") (pinfunction "NC_4") (pintype "no_connect"))
    )
    (net (code "65") (name "unconnected-(IC2-A0-Pad1)") (class "Default")
      (node (ref "IC2") (pin "1") (pinfunction "A0_1") (pintype "input"))
    )
    (net (code "66") (name "unconnected-(IC2-A1-Pad2)") (class "Default")
      (node (ref "IC2") (pin "2") (pinfunction "A1_2") (pintype "input"))
    )
    (net (code "67") (name "unconnected-(IC2-A2-Pad3)") (class "Default")
      (node (ref "IC2") (pin "3") (pinfunction "A2_3") (pintype "input"))
    )
    (net (code "68") (name "unconnected-(IC2-WP-Pad7)") (class "Default")
      (node (ref "IC2") (pin "7") (pinfunction "WP_7") (pintype "input"))
    )
    (net (code "69") (name "unconnected-(U1-A2_PB09(AIN3{slash}SER4:1{slash}TC4:1)-Pad8)") (class "Default")
      (node (ref "U1") (pin "8") (pinfunction "A2_PB09(AIN3/SER4:1/TC4:1)_8") (pintype "bidirectional"))
    )
    (net (code "70") (name "unconnected-(U4-ADC1-Pad16)") (class "Default")
      (node (ref "U4") (pin "16") (pinfunction "ADC1_16") (pintype "bidirectional"))
    )
    (net (code "71") (name "unconnected-(U4-ADC2-Pad15)") (class "Default")
      (node (ref "U4") (pin "15") (pinfunction "ADC2_15") (pintype "bidirectional"))
    )
    (net (code "72") (name "unconnected-(U4-ADC3-Pad13)") (class "Default")
      (node (ref "U4") (pin "13") (pinfunction "ADC3_13") (pintype "bidirectional"))
    )
    (net (code "73") (name "unconnected-(U4-INT1-Pad11)") (class "Default")
      (node (ref "U4") (pin "11") (pinfunction "INT1_11") (pintype "bidirectional"))
    )
  )
)
